# Sheet1.net
KiCad netlist of a schematic drawn in Altium Designer
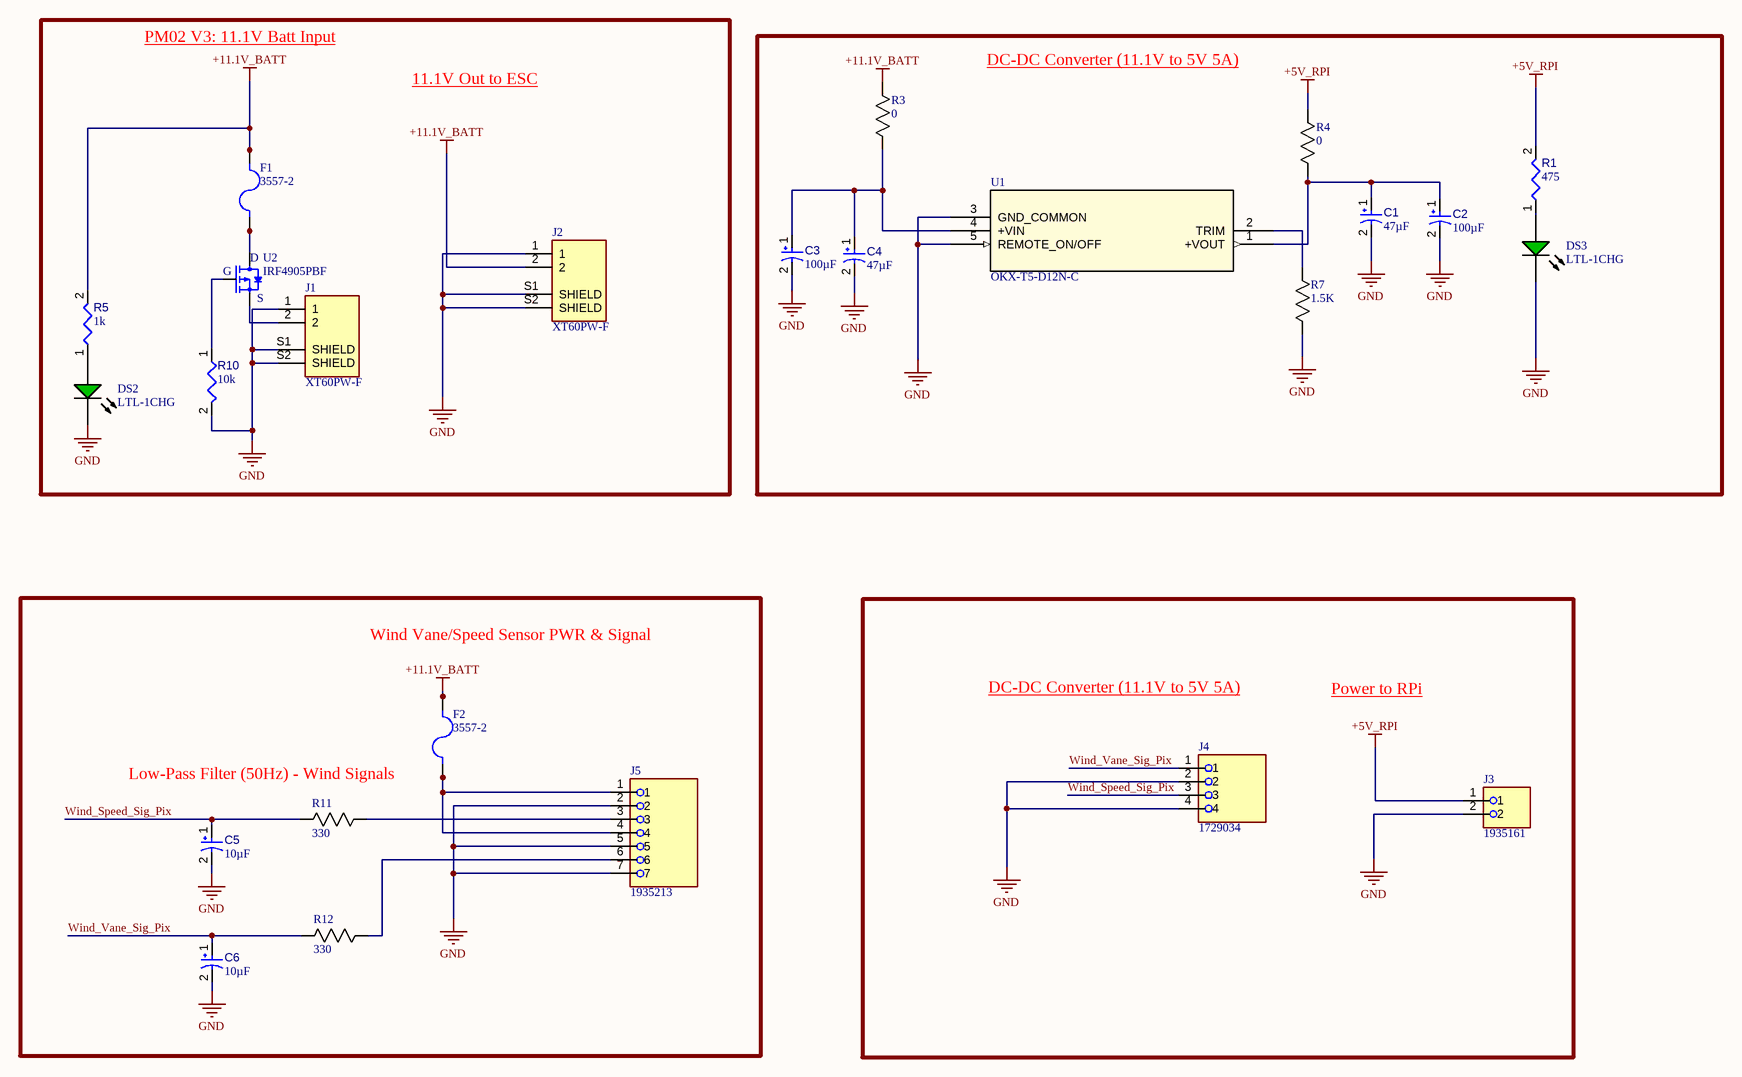
[diagram p0: Sheet1.SchDoc]

(export (version "E")
  (design (tool "Eeschema 10.0.6"))
  (components
    (comp (ref "C1")
      (value "47µF")
      (footprint "CAPPR55-250-1120X630X1220")
      (description "Aluminum Electrolytic Capacitor, 47 uF, +/-20%, 50 V, -40 to 85 degC, 2-Pin THD, RoHS, Bulk")
      (fields (field (name "TOLERANCE") "20%") (field (name "MANUFACTURER") "Panasonic"))
      (libsource (lib "George Cicero") (part "CAP-P-2"))
    )
    (comp (ref "C2")
      (value "100µF")
      (footprint "CAPPR65-350-1150X800X1250")
      (description "Aluminum Electrolytic Capacitor, 100 uF, +/- 20%, 50 V, -40 to 85 degC, 2-Pin THD, RoHS, Bulk")
      (fields (field (name "MANUFACTURER") "Panasonic") (field (name "TOLERANCE") "20%"))
      (libsource (lib "George Cicero") (part "CAP-P-2"))
    )
    (comp (ref "C3")
      (value "100µF")
      (footprint "CAPPR65-350-1150X800X1250")
      (description "Aluminum Electrolytic Capacitor, 100 uF, +/- 20%, 50 V, -40 to 85 degC, 2-Pin THD, RoHS, Bulk")
      (fields (field (name "MANUFACTURER") "Panasonic") (field (name "TOLERANCE") "20%"))
      (libsource (lib "George Cicero") (part "CAP-P-2"))
    )
    (comp (ref "C4")
      (value "47µF")
      (footprint "CAPPR55-250-1120X630X1220")
      (description "Aluminum Electrolytic Capacitor, 47 uF, +/-20%, 50 V, -40 to 85 degC, 2-Pin THD, RoHS, Bulk")
      (fields (field (name "TOLERANCE") "20%") (field (name "MANUFACTURER") "Panasonic"))
      (libsource (lib "George Cicero") (part "CAP-P-2"))
    )
    (comp (ref "C5")
      (value "10µF")
      (footprint "CAPPR55-200-1100X500X1200")
      (description "Aluminum Electrolytic Capacitor, 10 uF, +/- 20%, 50 V, -40 to 85 degC, 2-Pin THD, RoHS, Bulk")
      (fields (field (name "MANUFACTURER") "Panasonic") (field (name "TOLERANCE") "20%"))
      (libsource (lib "George Cicero") (part "CAP-P-2"))
    )
    (comp (ref "C6")
      (value "10µF")
      (footprint "CAPPR55-200-1100X500X1200")
      (description "Aluminum Electrolytic Capacitor, 10 uF, +/- 20%, 50 V, -40 to 85 degC, 2-Pin THD, RoHS, Bulk")
      (fields (field (name "MANUFACTURER") "Panasonic") (field (name "TOLERANCE") "20%"))
      (libsource (lib "") (part "CAP-P-2_1"))
    )
    (comp (ref "DS2")
      (value "LTL-1CHG")
      (footprint "LTST-LTL-1CHG-2")
      (description "LED Uni-Color Green, 100 mW, 30 mA, -55 to 100 degC, 2-Pin THD, RoHS, Bulk")
      (fields (field (name "POWER") "100mW") (field (name "MANUFACTURER") "Lite-On"))
      (libsource (lib "George Cicero") (part "LED-GREEN-AK-2"))
    )
    (comp (ref "DS3")
      (value "LTL-1CHG")
      (footprint "LTST-LTL-1CHG-2")
      (description "LED Uni-Color Green, 100 mW, 30 mA, -55 to 100 degC, 2-Pin THD, RoHS, Bulk")
      (fields (field (name "POWER") "100mW") (field (name "MANUFACTURER") "Lite-On"))
      (libsource (lib "George Cicero") (part "LED-GREEN-AK-2"))
    )
    (comp (ref "F1")
      (value "3557-2")
      (footprint "FUSE_3557-2")
      (description "THM 2 in 1 Auto Blade Holder")
      (fields (field (name "MF") "Keystone Electronics"))
      (libsource (lib "George Cicero") (part "3557-2"))
    )
    (comp (ref "F2")
      (value "3557-2")
      (footprint "FUSE_3557-2")
      (description "THM 2 in 1 Auto Blade Holder")
      (fields (field (name "MF") "Keystone Electronics"))
      (libsource (lib "George Cicero") (part "3557-2"))
    )
    (comp (ref "J1")
      (value "XT60PW-F")
      (footprint "AMASS_XT60PW-F")
      (description "Socket DC Supply Connector Female")
      (fields (field (name "MF") "AMASS"))
      (libsource (lib "George Cicero") (part "XT60PW-F"))
    )
    (comp (ref "J2")
      (value "XT60PW-F")
      (footprint "AMASS_XT60PW-F")
      (description "Socket DC Supply Connector Female")
      (fields (field (name "MF") "AMASS"))
      (libsource (lib "George Cicero") (part "XT60PW-F"))
    )
    (comp (ref "J3")
      (value "1935161")
      (footprint "PHOENIX_1935161")
      (description "PCB Terminal Screw 5mm 16AWG 400V 17.5A 2 Position COMBICON PT Series")
      (fields (field (name "MF") "Phoenix Contact"))
      (libsource (lib "George Cicero") (part "1935161"))
    )
    (comp (ref "J4")
      (value "1729034")
      (footprint "PHOENIX_1729034")
      (description "PCB Terminal Screw 5mm 16AWG 400V 13.5A 4 Position COMBICON MKDSN Series")
      (fields (field (name "MF") "Phoenix Contact"))
      (libsource (lib "George Cicero") (part "1729034"))
    )
    (comp (ref "J5")
      (value "1935213")
      (footprint "PHOENIX_1935213")
      (description "PCB Terminal Screw 5mm 16AWG 400V 17.5A 7 Position COMBICON PT Series")
      (fields (field (name "MF") "Phoenix Contact"))
      (libsource (lib "George Cicero") (part "1935213"))
    )
    (comp (ref "R1")
      (value "475")
      (footprint "RESA60-630X240")
      (description "Axial Resistor, 475 Ohm, +/- 1%, 0.25 W, -55 to 155 degC, 2-Pin THD, RoHS, Bulk")
      (fields (field (name "MANUFACTURER") "Yageo") (field (name "TOLERANCE") "1%"))
      (libsource (lib "George Cicero") (part "RES-2"))
    )
    (comp (ref "R3")
      (value "0")
      (footprint "RES_ZOR25_6P3X2P3_YAG")
      (description "RES 0 OHM JUMPER 1/4W AXIAL")
      (libsource (lib "George Cicero") (part "0"))
    )
    (comp (ref "R4")
      (value "0")
      (footprint "RES_ZOR25_6P3X2P3_YAG")
      (description "RES 0 OHM JUMPER 1/4W AXIAL")
      (libsource (lib "George Cicero") (part "0"))
    )
    (comp (ref "R5")
      (value "1k")
      (footprint "RESA60-630X240")
      (description "Axial Resistor, 1 KOhm, +/- 1%, 250 mW, -55 to 155 degC, 2-Pin THD, RoHS, Bulk")
      (fields (field (name "TOLERANCE") "1%") (field (name "POWER") "250mW"))
      (libsource (lib "George Cicero") (part "RES-2"))
    )
    (comp (ref "R7")
      (value "1.5K")
      (footprint "STA_CF14_STP")
      (description "RES 1.5K OHM 5% 1/4W AXIAL")
      (fields (field (name "MFR_PART_NUMBER") "CF14JT1K50"))
      (libsource (lib "George Cicero") (part "CF14JT1K50"))
    )
    (comp (ref "R10")
      (value "10k")
      (footprint "RESA60-630X240")
      (description "Axial Resistor, 10 KOhm, +/- 1%, 0.25 W, -55 to 155 degC, 2-Pin THD, RoHS, Bulk")
      (fields (field (name "TOLERANCE") "1%") (field (name "POWER") "250mW"))
      (libsource (lib "George Cicero") (part "RES-2"))
    )
    (comp (ref "R11")
      (value "330")
      (footprint "STA_CF14_STP")
      (description "RES 330 OHM 5% 1/4W AXIAL")
      (fields (field (name "Comment") "CF14JT330R"))
      (libsource (lib "George Cicero") (part "CF14JT330R"))
    )
    (comp (ref "R12")
      (value "330")
      (footprint "STA_CF14_STP")
      (description "RES 330 OHM 5% 1/4W AXIAL")
      (fields (field (name "Comment") "CF14JT330R"))
      (libsource (lib "George Cicero") (part "CF14JT330R"))
    )
    (comp (ref "U1")
      (value "OKX-T5-D12N-C")
      (footprint "OKX-T5-D12N-C_MUR")
      (description "No Description Available")
      (libsource (lib "George Cicero") (part "OKX-T5-D12N-C"))
    )
    (comp (ref "U2")
      (value "IRF4905PBF")
      (footprint "PG-TO220-3_INF")
      (description "No Description Available")
      (libsource (lib "George Cicero") (part "IRF4905PBF"))
    )
  )
  (nets
    (net (code "1") (name "+5V_RPI") (class "Default")
      (node (ref "J3") (pin "1") (pinfunction "1_1") (pintype "passive"))
      (node (ref "R1") (pin "2") (pinfunction "2_2") (pintype "passive"))
      (node (ref "R4") (pin "2") (pinfunction "2_2") (pintype "passive"))
    )
    (net (code "2") (name "+11.1V_BATT") (class "Default")
      (node (ref "F1") (pin "2_1") (pinfunction "2_2_1") (pintype "passive"))
      (node (ref "F1") (pin "2_2") (pinfunction "2_2_2") (pintype "passive"))
      (node (ref "F2") (pin "2_1") (pinfunction "2_2_1") (pintype "passive"))
      (node (ref "F2") (pin "2_2") (pinfunction "2_2_2") (pintype "passive"))
      (node (ref "J2") (pin "2") (pinfunction "2_2") (pintype "passive"))
      (node (ref "R3") (pin "2") (pinfunction "2_2") (pintype "passive"))
      (node (ref "R5") (pin "2") (pinfunction "2_2") (pintype "passive"))
    )
    (net (code "3") (name "/Wind_Speed_Sig_Pix") (class "Default")
      (node (ref "C5") (pin "1") (pinfunction "1_1") (pintype "passive"))
      (node (ref "J4") (pin "3") (pinfunction "3_3") (pintype "passive"))
      (node (ref "R11") (pin "1") (pinfunction "1_1") (pintype "passive"))
    )
    (net (code "4") (name "/Wind_Vane_Sig_Pix") (class "Default")
      (node (ref "C6") (pin "1") (pinfunction "1_1") (pintype "passive"))
      (node (ref "J4") (pin "1") (pinfunction "1_1") (pintype "passive"))
      (node (ref "R12") (pin "1") (pinfunction "1_1") (pintype "passive"))
    )
    (net (code "5") (name "GND") (class "Default")
      (node (ref "C1") (pin "2") (pinfunction "2_2") (pintype "passive"))
      (node (ref "C2") (pin "2") (pinfunction "2_2") (pintype "passive"))
      (node (ref "C3") (pin "2") (pinfunction "2_2") (pintype "passive"))
      (node (ref "C4") (pin "2") (pinfunction "2_2") (pintype "passive"))
      (node (ref "C5") (pin "2") (pinfunction "2_2") (pintype "passive"))
      (node (ref "C6") (pin "2") (pinfunction "2_2") (pintype "passive"))
      (node (ref "DS2") (pin "2") (pinfunction "K_2") (pintype "passive"))
      (node (ref "DS3") (pin "2") (pinfunction "K_2") (pintype "passive"))
      (node (ref "J1") (pin "1") (pinfunction "1_1") (pintype "passive"))
      (node (ref "J1") (pin "S1") (pinfunction "SHIELD_S1") (pintype "passive"))
      (node (ref "J1") (pin "S2") (pinfunction "SHIELD_S2") (pintype "passive"))
      (node (ref "J2") (pin "1") (pinfunction "1_1") (pintype "passive"))
      (node (ref "J2") (pin "S1") (pinfunction "SHIELD_S1") (pintype "passive"))
      (node (ref "J2") (pin "S2") (pinfunction "SHIELD_S2") (pintype "passive"))
      (node (ref "J3") (pin "2") (pinfunction "2_2") (pintype "passive"))
      (node (ref "J4") (pin "2") (pinfunction "2_2") (pintype "passive"))
      (node (ref "J4") (pin "4") (pinfunction "4_4") (pintype "passive"))
      (node (ref "J5") (pin "2") (pinfunction "2_2") (pintype "passive"))
      (node (ref "J5") (pin "5") (pinfunction "5_5") (pintype "passive"))
      (node (ref "J5") (pin "7") (pinfunction "7_7") (pintype "passive"))
      (node (ref "R10") (pin "2") (pinfunction "2_2") (pintype "passive"))
      (node (ref "R7") (pin "1") (pinfunction "1_1") (pintype "passive"))
      (node (ref "U1") (pin "3") (pinfunction "GND_COMMON_3") (pintype "power_in"))
      (node (ref "U1") (pin "5") (pinfunction "REMOTE_ON/OFF_5") (pintype "input"))
    )
    (net (code "6") (name "Net-(DS2-A)") (class "Default")
      (node (ref "DS2") (pin "1") (pinfunction "A_1") (pintype "passive"))
      (node (ref "R5") (pin "1") (pinfunction "1_1") (pintype "passive"))
    )
    (net (code "7") (name "Net-(DS3-A)") (class "Default")
      (node (ref "DS3") (pin "1") (pinfunction "A_1") (pintype "passive"))
      (node (ref "R1") (pin "1") (pinfunction "1_1") (pintype "passive"))
    )
    (net (code "8") (name "Net-(F2-1-Pad1_1)") (class "Default")
      (node (ref "F2") (pin "1_1") (pinfunction "1_1_1") (pintype "passive"))
      (node (ref "F2") (pin "1_2") (pinfunction "1_1_2") (pintype "passive"))
      (node (ref "J5") (pin "1") (pinfunction "1_1") (pintype "passive"))
      (node (ref "J5") (pin "4") (pinfunction "4_4") (pintype "passive"))
    )
    (net (code "9") (name "Net-(J5-Pad3)") (class "Default")
      (node (ref "J5") (pin "3") (pinfunction "3_3") (pintype "passive"))
      (node (ref "R11") (pin "2") (pinfunction "2_2") (pintype "passive"))
    )
    (net (code "10") (name "Net-(J5-Pad6)") (class "Default")
      (node (ref "J5") (pin "6") (pinfunction "6_6") (pintype "passive"))
      (node (ref "R12") (pin "2") (pinfunction "2_2") (pintype "passive"))
    )
    (net (code "11") (name "Net-(U1-+VIN)") (class "Default")
      (node (ref "C3") (pin "1") (pinfunction "1_1") (pintype "passive"))
      (node (ref "C4") (pin "1") (pinfunction "1_1") (pintype "passive"))
      (node (ref "R3") (pin "1") (pinfunction "1_1") (pintype "passive"))
      (node (ref "U1") (pin "4") (pinfunction "+VIN_4") (pintype "power_in"))
    )
    (net (code "12") (name "Net-(U1-+VOUT)") (class "Default")
      (node (ref "C1") (pin "1") (pinfunction "1_1") (pintype "passive"))
      (node (ref "C2") (pin "1") (pinfunction "1_1") (pintype "passive"))
      (node (ref "R4") (pin "1") (pinfunction "1_1") (pintype "passive"))
      (node (ref "U1") (pin "1") (pinfunction "+VOUT_1") (pintype "output"))
    )
    (net (code "13") (name "Net-(U1-TRIM)") (class "Default")
      (node (ref "R7") (pin "2") (pinfunction "2_2") (pintype "passive"))
      (node (ref "U1") (pin "2") (pinfunction "TRIM_2") (pintype "passive"))
    )
    (net (code "14") (name "Net-(U2-D)") (class "Default")
      (node (ref "F1") (pin "1_1") (pinfunction "1_1_1") (pintype "passive"))
      (node (ref "F1") (pin "1_2") (pinfunction "1_1_2") (pintype "passive"))
      (node (ref "U2") (pin "2") (pinfunction "D_2") (pintype "passive"))
    )
    (net (code "15") (name "Net-(U2-G)") (class "Default")
      (node (ref "R10") (pin "1") (pinfunction "1_1") (pintype "passive"))
      (node (ref "U2") (pin "1") (pinfunction "G_1") (pintype "passive"))
    )
    (net (code "16") (name "Net-(U2-S)") (class "Default")
      (node (ref "J1") (pin "2") (pinfunction "2_2") (pintype "passive"))
      (node (ref "U2") (pin "3") (pinfunction "S_3") (pintype "passive"))
    )
  )
)
